# CAN.net
KiCad netlist of a schematic drawn in Altium Designer
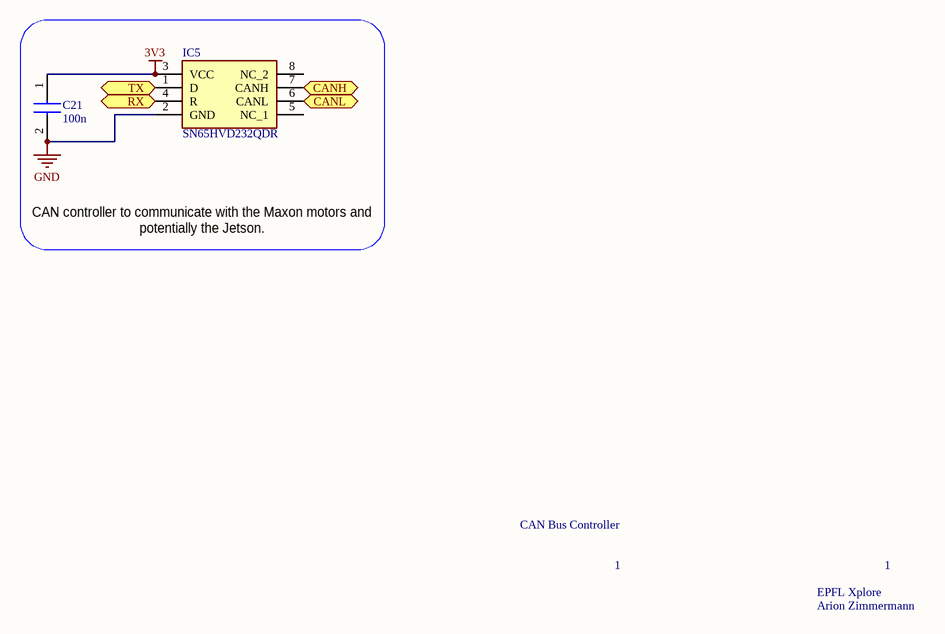
[diagram p0: CAN.SchDoc]

(export (version "E")
  (design (tool "Eeschema 10.0.6"))
  (components
    (comp (ref "C21")
      (value "100n")
      (footprint "SamacSys:CAPC1608X95N")
      (description "Capacitor")
      (fields
        (field (name "MANUFACTURER_PART_NUMBER") "C0603C104K5RACTU")
        (field (name "MOUSER PART NUMBER") "80-C0603C104K5R")
      )
      (libsource (lib "CarrierBoard") (part "C0603C104K5RACTU"))
    )
    (comp (ref "IC5")
      (value "SN65HVD232QDR")
      (footprint "SamacSys:SOIC127P600X175-8N")
      (description "Integrated Circuit")
      (fields (field (name "MOUSER PART NUMBER") "595-SN65HVD232QDR"))
      (libsource (lib "SamacSys") (part "SN65HVD232QDR"))
    )
  )
  (nets
    (net (code "1") (name "/CANH") (class "Default")
      (node (ref "IC5") (pin "7") (pinfunction "CANH_7") (pintype "passive"))
    )
    (net (code "2") (name "/CANL") (class "Default")
      (node (ref "IC5") (pin "6") (pinfunction "CANL_6") (pintype "passive"))
    )
    (net (code "3") (name "/RX") (class "Default")
      (node (ref "IC5") (pin "4") (pinfunction "R_4") (pintype "passive"))
    )
    (net (code "4") (name "/TX") (class "Default")
      (node (ref "IC5") (pin "1") (pinfunction "D_1") (pintype "passive"))
    )
    (net (code "5") (name "3V3") (class "Default")
      (node (ref "C21") (pin "1") (pinfunction "1_1") (pintype "passive"))
      (node (ref "IC5") (pin "3") (pinfunction "VCC_3") (pintype "passive"))
    )
    (net (code "6") (name "GND") (class "Default")
      (node (ref "C21") (pin "2") (pinfunction "2_2") (pintype "passive"))
      (node (ref "IC5") (pin "2") (pinfunction "GND_2") (pintype "passive"))
    )
    (net (code "7") (name "unconnected-(IC5-NC_1-Pad5)") (class "Default")
      (node (ref "IC5") (pin "5") (pinfunction "NC_1_5") (pintype "passive"))
    )
    (net (code "8") (name "unconnected-(IC5-NC_2-Pad8)") (class "Default")
      (node (ref "IC5") (pin "8") (pinfunction "NC_2_8") (pintype "passive"))
    )
  )
)
